# Sheet1.net
KiCad netlist of a schematic drawn in Altium Designer
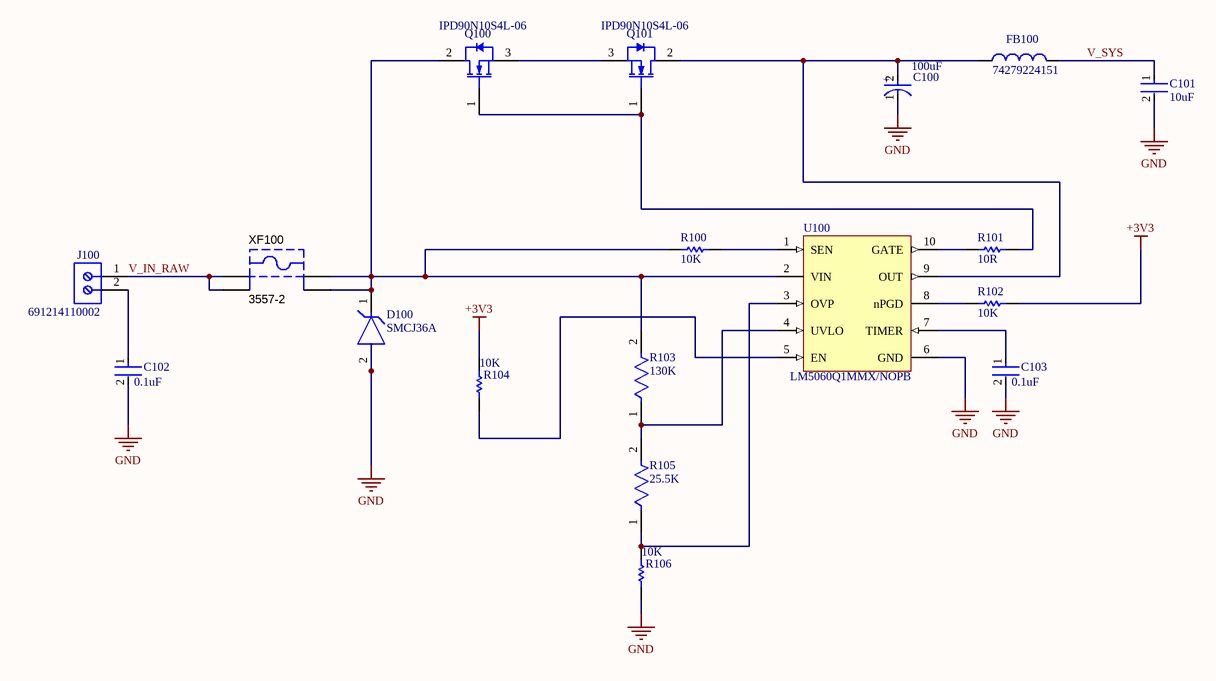
[diagram p0: Sheet1.SchDoc]

(export (version "E")
  (design (tool "Eeschema 10.0.6"))
  (components
    (comp (ref "C100")
      (value "100uF")
      (footprint "FP-RAD-TH-D_8_0_5-L_11_5-MFG")
      (description "Aluminum Electrolytic Capacitors (Radial Lead Type) 100uF ±20% 50V")
      (fields (field (name "VOLTAGE") "50V") (field (name "TOLERANCE") "20%"))
      (libsource (lib "Altium Content Vault") (part "a00bbbee19879c290e62620ae7e47b1"))
    )
    (comp (ref "C101")
      (value "10uF")
      (footprint "FP-C3225-250-0_4-IPC_A")
      (description "Multilayer Ceramic Capacitors 10uF ±10% 50V X7R SMD 1210")
      (libsource (lib "Altium Content Vault") (part "02cd4be3c70576c341d710602a673aa"))
    )
    (comp (ref "C102")
      (value "0.1uF")
      (footprint "FP-C1206C-EB-MFG")
      (description "CAP CER 0.1UF 50V X7R 1206")
      (fields
        (field (name "MANUFACTURER") "KEMET")
        (field (name "OCTOPART") "https://octopart.com/c1206c104k5racauto-kemet-12595586")
      )
      (libsource (lib "Altium Content Vault") (part "b4654b650e69147ec39a6b967a45e02"))
    )
    (comp (ref "C103")
      (value "0.1uF")
      (footprint "FP-C1206C-EB-MFG")
      (description "CAP CER 0.1UF 50V X7R 1206")
      (fields
        (field (name "MANUFACTURER") "KEMET")
        (field (name "OCTOPART") "https://octopart.com/c1206c104k5racauto-kemet-12595586")
      )
      (libsource (lib "Altium Content Vault") (part "b4654b650e69147ec39a6b967a45e02"))
    )
    (comp (ref "D100")
      (value "SMCJ36A")
      (footprint "FP-SMCJ-MFG")
      (description "TVS DIODE 36V 58.1V DO214AB")
      (libsource (lib "Altium Content Vault") (part "f813f71cba58e380607f5dd3caf9714"))
    )
    (comp (ref "FB100")
      (value "74279224151")
      (footprint "WE-MPSB_2220_L5.6W5.1H1.8")
      (fields (field (name "TOLERANCE") "25%"))
      (libsource (lib "Altium Content Vault") (part "Ferrite"))
    )
    (comp (ref "J100")
      (value "691214110002")
      (footprint "691214110002")
      (description "2141 Series 3.5MM Pitch Straight, Pcb Terminal Block, Through Hole, 2 Way")
      (fields (field (name "VOLTAGE") "300V"))
      (libsource (lib "Altium Content Vault") (part "TBL - 1R - 02P - Screw"))
    )
    (comp (ref "Q100")
      (value "IPD90N10S4L-06")
      (footprint "INF-PG-TO252-3-313_M")
      (description "OptiMOS-T2 Power-Transistor, 100 V VDS, 90 A ID, PG-TO252-3-313, Reel, Green")
      (fields (field (name "MANUFACTURER") "Infineon"))
      (libsource (lib "Altium Content Vault") (part "INF-MOSFET-N-3"))
    )
    (comp (ref "Q101")
      (value "IPD90N10S4L-06")
      (footprint "INF-PG-TO252-3-313_M")
      (description "OptiMOS-T2 Power-Transistor, 100 V VDS, 90 A ID, PG-TO252-3-313, Reel, Green")
      (fields (field (name "MANUFACTURER") "Infineon"))
      (libsource (lib "Altium Content Vault") (part "INF-MOSFET-N-3"))
    )
    (comp (ref "R100")
      (value "10K")
      (footprint "RESC1609X50X30NL8T20")
      (description "Chip Resistor, 10 KOhm, +/- 1%, 100 mW, -55 to 155 degC, 0603 (1608 Metric), RoHS, Tape and Reel")
      (fields (field (name "MANUFACTURER") "Vishay Semiconductor"))
      (libsource (lib "Altium Content Vault") (part "RES-2"))
    )
    (comp (ref "R101")
      (value "10R")
      (footprint "RESC1608X55X25NL10T15")
      (description "Chip Resistor, 10 Ohm, +/- 1%, 0.1 W, -55 to 155 degC, 0603 (1608 Metric), RoHS, Tape and Reel")
      (fields (field (name "MANUFACTURER") "Yageo"))
      (libsource (lib "Altium Content Vault") (part "RES-2"))
    )
    (comp (ref "R102")
      (value "10K")
      (footprint "RESC1609X50X30NL8T20")
      (description "Chip Resistor, 10 KOhm, +/- 1%, 100 mW, -55 to 155 degC, 0603 (1608 Metric), RoHS, Tape and Reel")
      (fields (field (name "MANUFACTURER") "Vishay Semiconductor"))
      (libsource (lib "Altium Content Vault") (part "RES-2"))
    )
    (comp (ref "R103")
      (value "130K")
      (footprint "FP-CRCW0603-e3-IPC_C")
      (description "RES Thick Film, 130kΩ, 1%, 0.1W, 100ppm/°C, 0603")
      (fields (field (name "TOLERANCE") "1%"))
      (libsource (lib "Altium Content Vault") (part "1029c3af85768c4190bb7ad29bc67b5"))
    )
    (comp (ref "R104")
      (value "10K")
      (footprint "RESC1609X50X30NL8T20")
      (description "Chip Resistor, 10 KOhm, +/- 1%, 100 mW, -55 to 155 degC, 0603 (1608 Metric), RoHS, Tape and Reel")
      (fields (field (name "MANUFACTURER") "Vishay Semiconductor"))
      (libsource (lib "Altium Content Vault") (part "RES-2"))
    )
    (comp (ref "R105")
      (value "25.5K")
      (footprint "FP-CRCW0603-e3-IPC_A")
      (description "RES Thick Film, 25.5kΩ, 1%, 0.1W, 100ppm/°C, 0603")
      (fields (field (name "TOLERANCE") "1%"))
      (libsource (lib "Altium Content Vault") (part "1029c3af85768c4190bb7ad29bc67b5"))
    )
    (comp (ref "R106")
      (value "10K")
      (footprint "RESC1609X50X30NL8T20")
      (description "Chip Resistor, 10 KOhm, +/- 1%, 100 mW, -55 to 155 degC, 0603 (1608 Metric), RoHS, Tape and Reel")
      (fields (field (name "MANUFACTURER") "Vishay Semiconductor"))
      (libsource (lib "Altium Content Vault") (part "RES-2"))
    )
    (comp (ref "U100")
      (value "LM5060Q1MMX/NOPB")
      (footprint "DGS0010A_M")
      (description "High-Side Protection Controller with Low Quiescent Current, 10-pin MSOP, Pb-Free")
      (fields (field (name "MANUFACTURER") "Texas Instruments"))
      (libsource (lib "Altium Content Vault") (part "PM-CNTL-LM5060MM-10"))
    )
    (comp (ref "XF100")
      (value "3557-2")
      (footprint "KSTN-3557-2")
      (description "FUSE HOLDER, PCB MOUNT, 500VAC, 20A, ROHS")
      (fields (field (name "VOLTAGE") "500V") (field (name "MANUFACTURER") "Keystone-Electronics"))
      (libsource (lib "Altium Content Vault") (part "FUSE_HOLDER-4"))
    )
  )
  (nets
    (net (code "1") (name "+3V3") (class "Default")
      (node (ref "R102") (pin "1") (pinfunction "1_1") (pintype "passive"))
      (node (ref "R104") (pin "2") (pinfunction "2_2") (pintype "passive"))
    )
    (net (code "2") (name "/V_IN_RAW") (class "Default")
      (node (ref "J100") (pin "1") (pinfunction "1_1") (pintype "passive"))
      (node (ref "XF100") (pin "1") (pinfunction "1_1") (pintype "passive"))
      (node (ref "XF100") (pin "2") (pinfunction "2_2") (pintype "passive"))
    )
    (net (code "3") (name "/V_SYS") (class "Default")
      (node (ref "C101") (pin "1") (pinfunction "1_1") (pintype "passive"))
      (node (ref "FB100") (pin "2") (pinfunction "2_2") (pintype "passive"))
    )
    (net (code "4") (name "GND") (class "Default")
      (node (ref "C100") (pin "1") (pinfunction "C_1") (pintype "passive"))
      (node (ref "C101") (pin "2") (pinfunction "2_2") (pintype "passive"))
      (node (ref "C102") (pin "2") (pinfunction "2_2") (pintype "passive"))
      (node (ref "C103") (pin "2") (pinfunction "2_2") (pintype "passive"))
      (node (ref "D100") (pin "2") (pinfunction "A_2") (pintype "passive"))
      (node (ref "R106") (pin "1") (pinfunction "1_1") (pintype "passive"))
      (node (ref "U100") (pin "6") (pinfunction "GND_6") (pintype "power_in"))
    )
    (net (code "5") (name "Net-(C100-A)") (class "Default")
      (node (ref "C100") (pin "2") (pinfunction "A_2") (pintype "passive"))
      (node (ref "FB100") (pin "1") (pinfunction "1_1") (pintype "passive"))
      (node (ref "Q101") (pin "2") (pinfunction "DRAIN_2") (pintype "passive"))
      (node (ref "U100") (pin "9") (pinfunction "OUT_9") (pintype "output"))
    )
    (net (code "6") (name "Net-(C102-Pad1)") (class "Default")
      (node (ref "C102") (pin "1") (pinfunction "1_1") (pintype "passive"))
      (node (ref "J100") (pin "2") (pinfunction "2_2") (pintype "passive"))
    )
    (net (code "7") (name "Net-(D100-C)") (class "Default")
      (node (ref "D100") (pin "1") (pinfunction "C_1") (pintype "passive"))
      (node (ref "Q100") (pin "2") (pinfunction "DRAIN_2") (pintype "passive"))
      (node (ref "R100") (pin "2") (pinfunction "2_2") (pintype "passive"))
      (node (ref "R103") (pin "2") (pinfunction "2_2") (pintype "passive"))
      (node (ref "U100") (pin "2") (pinfunction "VIN_2") (pintype "power_in"))
      (node (ref "XF100") (pin "3") (pinfunction "3_3") (pintype "passive"))
      (node (ref "XF100") (pin "4") (pinfunction "4_4") (pintype "passive"))
    )
    (net (code "8") (name "Net-(Q100-GATE)") (class "Default")
      (node (ref "Q100") (pin "1") (pinfunction "GATE_1") (pintype "passive"))
      (node (ref "Q101") (pin "1") (pinfunction "GATE_1") (pintype "passive"))
      (node (ref "R101") (pin "2") (pinfunction "2_2") (pintype "passive"))
    )
    (net (code "9") (name "Net-(Q100-SOURCE)") (class "Default")
      (node (ref "Q100") (pin "3") (pinfunction "SOURCE_3") (pintype "passive"))
      (node (ref "Q101") (pin "3") (pinfunction "SOURCE_3") (pintype "passive"))
    )
    (net (code "10") (name "Net-(U100-EN)") (class "Default")
      (node (ref "R104") (pin "1") (pinfunction "1_1") (pintype "passive"))
      (node (ref "U100") (pin "5") (pinfunction "EN_5") (pintype "input"))
    )
    (net (code "11") (name "Net-(U100-GATE)") (class "Default")
      (node (ref "R101") (pin "1") (pinfunction "1_1") (pintype "passive"))
      (node (ref "U100") (pin "10") (pinfunction "GATE_10") (pintype "output"))
    )
    (net (code "12") (name "Net-(U100-OVP)") (class "Default")
      (node (ref "R105") (pin "1") (pinfunction "1_1") (pintype "passive"))
      (node (ref "R106") (pin "2") (pinfunction "2_2") (pintype "passive"))
      (node (ref "U100") (pin "3") (pinfunction "OVP_3") (pintype "input"))
    )
    (net (code "13") (name "Net-(U100-SEN)") (class "Default")
      (node (ref "R100") (pin "1") (pinfunction "1_1") (pintype "passive"))
      (node (ref "U100") (pin "1") (pinfunction "SEN_1") (pintype "input"))
    )
    (net (code "14") (name "Net-(U100-TIMER)") (class "Default")
      (node (ref "C103") (pin "1") (pinfunction "1_1") (pintype "passive"))
      (node (ref "U100") (pin "7") (pinfunction "TIMER_7") (pintype "input"))
    )
    (net (code "15") (name "Net-(U100-UVLO)") (class "Default")
      (node (ref "R103") (pin "1") (pinfunction "1_1") (pintype "passive"))
      (node (ref "R105") (pin "2") (pinfunction "2_2") (pintype "passive"))
      (node (ref "U100") (pin "4") (pinfunction "UVLO_4") (pintype "input"))
    )
    (net (code "16") (name "Net-(U100-nPGD)") (class "Default")
      (node (ref "R102") (pin "2") (pinfunction "2_2") (pintype "passive"))
      (node (ref "U100") (pin "8") (pinfunction "nPGD_8") (pintype "open_collector"))
    )
  )
)
